# LuMini_1Inch.net
KiCad netlist of a schematic drawn in EAGLE
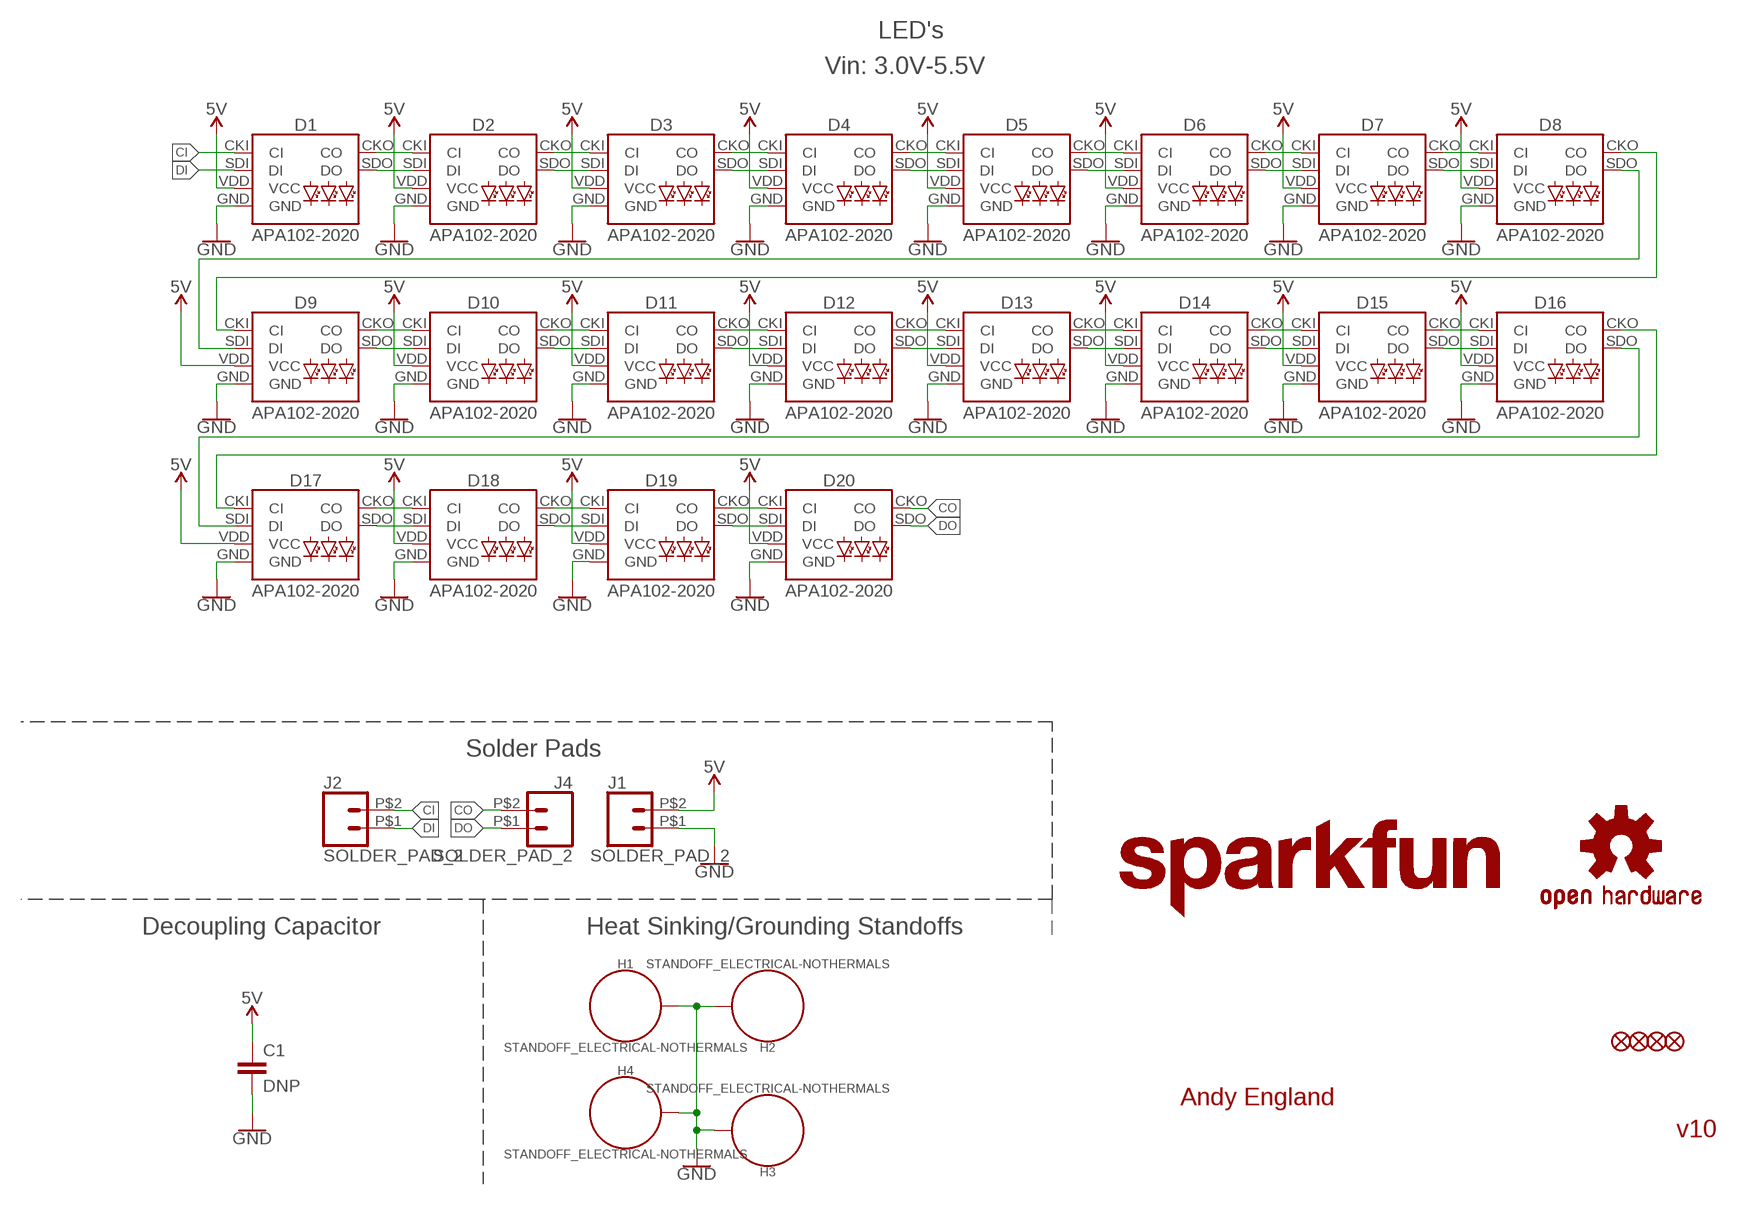
[diagram p0: schematic, sheet 1]

(export (version "E")
  (design (tool "Eeschema 10.0.6"))
  (components
    (comp (ref "C1")
      (value "DNP")
      (footprint "eagle-import:0603")
      (libsource (lib "eagle-import") (part "4.7UF-0603-6.3V-(10%)"))
    )
    (comp (ref "D1")
      (value "APA102-2020")
      (footprint "eagle-import:APA102-2020")
      (libsource (lib "eagle-import") (part "APA102-2020"))
    )
    (comp (ref "D2")
      (value "APA102-2020")
      (footprint "eagle-import:APA102-2020")
      (libsource (lib "eagle-import") (part "APA102-2020"))
    )
    (comp (ref "D3")
      (value "APA102-2020")
      (footprint "eagle-import:APA102-2020")
      (libsource (lib "eagle-import") (part "APA102-2020"))
    )
    (comp (ref "D4")
      (value "APA102-2020")
      (footprint "eagle-import:APA102-2020")
      (libsource (lib "eagle-import") (part "APA102-2020"))
    )
    (comp (ref "D5")
      (value "APA102-2020")
      (footprint "eagle-import:APA102-2020")
      (libsource (lib "eagle-import") (part "APA102-2020"))
    )
    (comp (ref "D6")
      (value "APA102-2020")
      (footprint "eagle-import:APA102-2020")
      (libsource (lib "eagle-import") (part "APA102-2020"))
    )
    (comp (ref "D7")
      (value "APA102-2020")
      (footprint "eagle-import:APA102-2020")
      (libsource (lib "eagle-import") (part "APA102-2020"))
    )
    (comp (ref "D8")
      (value "APA102-2020")
      (footprint "eagle-import:APA102-2020")
      (libsource (lib "eagle-import") (part "APA102-2020"))
    )
    (comp (ref "D9")
      (value "APA102-2020")
      (footprint "eagle-import:APA102-2020")
      (libsource (lib "eagle-import") (part "APA102-2020"))
    )
    (comp (ref "D10")
      (value "APA102-2020")
      (footprint "eagle-import:APA102-2020")
      (libsource (lib "eagle-import") (part "APA102-2020"))
    )
    (comp (ref "D11")
      (value "APA102-2020")
      (footprint "eagle-import:APA102-2020")
      (libsource (lib "eagle-import") (part "APA102-2020"))
    )
    (comp (ref "D12")
      (value "APA102-2020")
      (footprint "eagle-import:APA102-2020")
      (libsource (lib "eagle-import") (part "APA102-2020"))
    )
    (comp (ref "D13")
      (value "APA102-2020")
      (footprint "eagle-import:APA102-2020")
      (libsource (lib "eagle-import") (part "APA102-2020"))
    )
    (comp (ref "D14")
      (value "APA102-2020")
      (footprint "eagle-import:APA102-2020")
      (libsource (lib "eagle-import") (part "APA102-2020"))
    )
    (comp (ref "D15")
      (value "APA102-2020")
      (footprint "eagle-import:APA102-2020")
      (libsource (lib "eagle-import") (part "APA102-2020"))
    )
    (comp (ref "D16")
      (value "APA102-2020")
      (footprint "eagle-import:APA102-2020")
      (libsource (lib "eagle-import") (part "APA102-2020"))
    )
    (comp (ref "D17")
      (value "APA102-2020")
      (footprint "eagle-import:APA102-2020")
      (libsource (lib "eagle-import") (part "APA102-2020"))
    )
    (comp (ref "D18")
      (value "APA102-2020")
      (footprint "eagle-import:APA102-2020")
      (libsource (lib "eagle-import") (part "APA102-2020"))
    )
    (comp (ref "D19")
      (value "APA102-2020")
      (footprint "eagle-import:APA102-2020")
      (libsource (lib "eagle-import") (part "APA102-2020"))
    )
    (comp (ref "D20")
      (value "APA102-2020")
      (footprint "eagle-import:APA102-2020")
      (libsource (lib "eagle-import") (part "APA102-2020"))
    )
    (comp (ref "FD1")
      (value "FIDUCIALUFIDUCIAL")
      (footprint "eagle-import:FIDUCIAL-MICRO")
      (libsource (lib "eagle-import") (part "FIDUCIALUFIDUCIAL"))
    )
    (comp (ref "FD2")
      (value "FIDUCIALUFIDUCIAL")
      (footprint "eagle-import:FIDUCIAL-MICRO")
      (libsource (lib "eagle-import") (part "FIDUCIALUFIDUCIAL"))
    )
    (comp (ref "FD3")
      (value "FIDUCIALUFIDUCIAL")
      (footprint "eagle-import:FIDUCIAL-MICRO")
      (libsource (lib "eagle-import") (part "FIDUCIALUFIDUCIAL"))
    )
    (comp (ref "FD4")
      (value "FIDUCIALUFIDUCIAL")
      (footprint "eagle-import:FIDUCIAL-MICRO")
      (libsource (lib "eagle-import") (part "FIDUCIALUFIDUCIAL"))
    )
    (comp (ref "H1")
      (value "STANDOFF_ELECTRICAL-NOTHERMALS")
      (footprint "eagle-import:STANDOFF-ELECTRICAL-NOTHERMALS")
      (libsource (lib "eagle-import") (part "STANDOFF_ELECTRICAL-NOTHERMALS"))
    )
    (comp (ref "H2")
      (value "STANDOFF_ELECTRICAL-NOTHERMALS")
      (footprint "eagle-import:STANDOFF-ELECTRICAL-NOTHERMALS")
      (libsource (lib "eagle-import") (part "STANDOFF_ELECTRICAL-NOTHERMALS"))
    )
    (comp (ref "H3")
      (value "STANDOFF_ELECTRICAL-NOTHERMALS")
      (footprint "eagle-import:STANDOFF-ELECTRICAL-NOTHERMALS")
      (libsource (lib "eagle-import") (part "STANDOFF_ELECTRICAL-NOTHERMALS"))
    )
    (comp (ref "H4")
      (value "STANDOFF_ELECTRICAL-NOTHERMALS")
      (footprint "eagle-import:STANDOFF-ELECTRICAL-NOTHERMALS")
      (libsource (lib "eagle-import") (part "STANDOFF_ELECTRICAL-NOTHERMALS"))
    )
    (comp (ref "J1")
      (value "SOLDER_PAD_2")
      (footprint "eagle-import:SOLDER_PAD_2")
      (libsource (lib "eagle-import") (part "SOLDER_PAD_2"))
    )
    (comp (ref "J2")
      (value "SOLDER_PAD_2")
      (footprint "eagle-import:SOLDER_PAD_2")
      (libsource (lib "eagle-import") (part "SOLDER_PAD_2"))
    )
    (comp (ref "J4")
      (value "SOLDER_PAD_2")
      (footprint "eagle-import:SOLDER_PAD_2")
      (libsource (lib "eagle-import") (part "SOLDER_PAD_2"))
    )
    (comp (ref "LOGO1")
      (value "SFE_LOGO_NAME.1_INCH")
      (footprint "eagle-import:SFE_LOGO_NAME_.1")
      (libsource (lib "eagle-import") (part "SFE_LOGO_NAME.1_INCH"))
    )
    (comp (ref "LOGO2")
      (value "OSHW-LOGOS")
      (footprint "eagle-import:OSHW-LOGO-S")
      (libsource (lib "eagle-import") (part "OSHW-LOGOS"))
    )
  )
  (nets
    (net (code "1") (name "5V") (class "Default")
      (node (ref "C1") (pin "1") (pinfunction "1_1") (pintype "passive"))
      (node (ref "D1") (pin "VDD") (pinfunction "VCC_VDD") (pintype "bidirectional"))
      (node (ref "D10") (pin "VDD") (pinfunction "VCC_VDD") (pintype "bidirectional"))
      (node (ref "D11") (pin "VDD") (pinfunction "VCC_VDD") (pintype "bidirectional"))
      (node (ref "D12") (pin "VDD") (pinfunction "VCC_VDD") (pintype "bidirectional"))
      (node (ref "D13") (pin "VDD") (pinfunction "VCC_VDD") (pintype "bidirectional"))
      (node (ref "D14") (pin "VDD") (pinfunction "VCC_VDD") (pintype "bidirectional"))
      (node (ref "D15") (pin "VDD") (pinfunction "VCC_VDD") (pintype "bidirectional"))
      (node (ref "D16") (pin "VDD") (pinfunction "VCC_VDD") (pintype "bidirectional"))
      (node (ref "D17") (pin "VDD") (pinfunction "VCC_VDD") (pintype "bidirectional"))
      (node (ref "D18") (pin "VDD") (pinfunction "VCC_VDD") (pintype "bidirectional"))
      (node (ref "D19") (pin "VDD") (pinfunction "VCC_VDD") (pintype "bidirectional"))
      (node (ref "D2") (pin "VDD") (pinfunction "VCC_VDD") (pintype "bidirectional"))
      (node (ref "D20") (pin "VDD") (pinfunction "VCC_VDD") (pintype "bidirectional"))
      (node (ref "D3") (pin "VDD") (pinfunction "VCC_VDD") (pintype "bidirectional"))
      (node (ref "D4") (pin "VDD") (pinfunction "VCC_VDD") (pintype "bidirectional"))
      (node (ref "D5") (pin "VDD") (pinfunction "VCC_VDD") (pintype "bidirectional"))
      (node (ref "D6") (pin "VDD") (pinfunction "VCC_VDD") (pintype "bidirectional"))
      (node (ref "D7") (pin "VDD") (pinfunction "VCC_VDD") (pintype "bidirectional"))
      (node (ref "D8") (pin "VDD") (pinfunction "VCC_VDD") (pintype "bidirectional"))
      (node (ref "D9") (pin "VDD") (pinfunction "VCC_VDD") (pintype "bidirectional"))
      (node (ref "J1") (pin "P$2") (pinfunction "2_P$2") (pintype "passive"))
    )
    (net (code "2") (name "CI") (class "Default")
      (node (ref "D1") (pin "CKI") (pinfunction "CI_CKI") (pintype "bidirectional"))
      (node (ref "J2") (pin "P$2") (pinfunction "2_P$2") (pintype "passive"))
    )
    (net (code "3") (name "CO") (class "Default")
      (node (ref "D20") (pin "CKO") (pinfunction "CO_CKO") (pintype "bidirectional"))
      (node (ref "J4") (pin "P$2") (pinfunction "2_P$2") (pintype "passive"))
    )
    (net (code "4") (name "DI") (class "Default")
      (node (ref "D1") (pin "SDI") (pinfunction "DI_SDI") (pintype "bidirectional"))
      (node (ref "J2") (pin "P$1") (pinfunction "1_P$1") (pintype "passive"))
    )
    (net (code "5") (name "DO") (class "Default")
      (node (ref "D20") (pin "SDO") (pinfunction "DO_SDO") (pintype "bidirectional"))
      (node (ref "J4") (pin "P$1") (pinfunction "1_P$1") (pintype "passive"))
    )
    (net (code "6") (name "GND") (class "Default")
      (node (ref "C1") (pin "2") (pinfunction "2_2") (pintype "passive"))
      (node (ref "D1") (pin "GND") (pinfunction "GND_GND") (pintype "bidirectional"))
      (node (ref "D10") (pin "GND") (pinfunction "GND_GND") (pintype "bidirectional"))
      (node (ref "D11") (pin "GND") (pinfunction "GND_GND") (pintype "bidirectional"))
      (node (ref "D12") (pin "GND") (pinfunction "GND_GND") (pintype "bidirectional"))
      (node (ref "D13") (pin "GND") (pinfunction "GND_GND") (pintype "bidirectional"))
      (node (ref "D14") (pin "GND") (pinfunction "GND_GND") (pintype "bidirectional"))
      (node (ref "D15") (pin "GND") (pinfunction "GND_GND") (pintype "bidirectional"))
      (node (ref "D16") (pin "GND") (pinfunction "GND_GND") (pintype "bidirectional"))
      (node (ref "D17") (pin "GND") (pinfunction "GND_GND") (pintype "bidirectional"))
      (node (ref "D18") (pin "GND") (pinfunction "GND_GND") (pintype "bidirectional"))
      (node (ref "D19") (pin "GND") (pinfunction "GND_GND") (pintype "bidirectional"))
      (node (ref "D2") (pin "GND") (pinfunction "GND_GND") (pintype "bidirectional"))
      (node (ref "D20") (pin "GND") (pinfunction "GND_GND") (pintype "bidirectional"))
      (node (ref "D3") (pin "GND") (pinfunction "GND_GND") (pintype "bidirectional"))
      (node (ref "D4") (pin "GND") (pinfunction "GND_GND") (pintype "bidirectional"))
      (node (ref "D5") (pin "GND") (pinfunction "GND_GND") (pintype "bidirectional"))
      (node (ref "D6") (pin "GND") (pinfunction "GND_GND") (pintype "bidirectional"))
      (node (ref "D7") (pin "GND") (pinfunction "GND_GND") (pintype "bidirectional"))
      (node (ref "D8") (pin "GND") (pinfunction "GND_GND") (pintype "bidirectional"))
      (node (ref "D9") (pin "GND") (pinfunction "GND_GND") (pintype "bidirectional"))
      (node (ref "H1") (pin "P1") (pinfunction "P$1_P1") (pintype "bidirectional"))
      (node (ref "H2") (pin "P1") (pinfunction "P$1_P1") (pintype "bidirectional"))
      (node (ref "H3") (pin "P1") (pinfunction "P$1_P1") (pintype "bidirectional"))
      (node (ref "H4") (pin "P1") (pinfunction "P$1_P1") (pintype "bidirectional"))
      (node (ref "J1") (pin "P$1") (pinfunction "1_P$1") (pintype "passive"))
    )
    (net (code "7") (name "Net-(D1-CO)") (class "Default")
      (node (ref "D1") (pin "CKO") (pinfunction "CO_CKO") (pintype "bidirectional"))
      (node (ref "D2") (pin "CKI") (pinfunction "CI_CKI") (pintype "bidirectional"))
    )
    (net (code "8") (name "Net-(D1-DO)") (class "Default")
      (node (ref "D1") (pin "SDO") (pinfunction "DO_SDO") (pintype "bidirectional"))
      (node (ref "D2") (pin "SDI") (pinfunction "DI_SDI") (pintype "bidirectional"))
    )
    (net (code "9") (name "Net-(D2-CO)") (class "Default")
      (node (ref "D2") (pin "CKO") (pinfunction "CO_CKO") (pintype "bidirectional"))
      (node (ref "D3") (pin "CKI") (pinfunction "CI_CKI") (pintype "bidirectional"))
    )
    (net (code "10") (name "Net-(D2-DO)") (class "Default")
      (node (ref "D2") (pin "SDO") (pinfunction "DO_SDO") (pintype "bidirectional"))
      (node (ref "D3") (pin "SDI") (pinfunction "DI_SDI") (pintype "bidirectional"))
    )
    (net (code "11") (name "Net-(D3-CO)") (class "Default")
      (node (ref "D3") (pin "CKO") (pinfunction "CO_CKO") (pintype "bidirectional"))
      (node (ref "D4") (pin "CKI") (pinfunction "CI_CKI") (pintype "bidirectional"))
    )
    (net (code "12") (name "Net-(D3-DO)") (class "Default")
      (node (ref "D3") (pin "SDO") (pinfunction "DO_SDO") (pintype "bidirectional"))
      (node (ref "D4") (pin "SDI") (pinfunction "DI_SDI") (pintype "bidirectional"))
    )
    (net (code "13") (name "Net-(D4-CO)") (class "Default")
      (node (ref "D4") (pin "CKO") (pinfunction "CO_CKO") (pintype "bidirectional"))
      (node (ref "D5") (pin "CKI") (pinfunction "CI_CKI") (pintype "bidirectional"))
    )
    (net (code "14") (name "Net-(D4-DO)") (class "Default")
      (node (ref "D4") (pin "SDO") (pinfunction "DO_SDO") (pintype "bidirectional"))
      (node (ref "D5") (pin "SDI") (pinfunction "DI_SDI") (pintype "bidirectional"))
    )
    (net (code "15") (name "Net-(D5-CO)") (class "Default")
      (node (ref "D5") (pin "CKO") (pinfunction "CO_CKO") (pintype "bidirectional"))
      (node (ref "D6") (pin "CKI") (pinfunction "CI_CKI") (pintype "bidirectional"))
    )
    (net (code "16") (name "Net-(D5-DO)") (class "Default")
      (node (ref "D5") (pin "SDO") (pinfunction "DO_SDO") (pintype "bidirectional"))
      (node (ref "D6") (pin "SDI") (pinfunction "DI_SDI") (pintype "bidirectional"))
    )
    (net (code "17") (name "Net-(D6-CO)") (class "Default")
      (node (ref "D6") (pin "CKO") (pinfunction "CO_CKO") (pintype "bidirectional"))
      (node (ref "D7") (pin "CKI") (pinfunction "CI_CKI") (pintype "bidirectional"))
    )
    (net (code "18") (name "Net-(D6-DO)") (class "Default")
      (node (ref "D6") (pin "SDO") (pinfunction "DO_SDO") (pintype "bidirectional"))
      (node (ref "D7") (pin "SDI") (pinfunction "DI_SDI") (pintype "bidirectional"))
    )
    (net (code "19") (name "Net-(D7-CO)") (class "Default")
      (node (ref "D7") (pin "CKO") (pinfunction "CO_CKO") (pintype "bidirectional"))
      (node (ref "D8") (pin "CKI") (pinfunction "CI_CKI") (pintype "bidirectional"))
    )
    (net (code "20") (name "Net-(D7-DO)") (class "Default")
      (node (ref "D7") (pin "SDO") (pinfunction "DO_SDO") (pintype "bidirectional"))
      (node (ref "D8") (pin "SDI") (pinfunction "DI_SDI") (pintype "bidirectional"))
    )
    (net (code "21") (name "Net-(D8-CO)") (class "Default")
      (node (ref "D8") (pin "CKO") (pinfunction "CO_CKO") (pintype "bidirectional"))
      (node (ref "D9") (pin "CKI") (pinfunction "CI_CKI") (pintype "bidirectional"))
    )
    (net (code "22") (name "Net-(D8-DO)") (class "Default")
      (node (ref "D8") (pin "SDO") (pinfunction "DO_SDO") (pintype "bidirectional"))
      (node (ref "D9") (pin "SDI") (pinfunction "DI_SDI") (pintype "bidirectional"))
    )
    (net (code "23") (name "Net-(D10-CI)") (class "Default")
      (node (ref "D10") (pin "CKI") (pinfunction "CI_CKI") (pintype "bidirectional"))
      (node (ref "D9") (pin "CKO") (pinfunction "CO_CKO") (pintype "bidirectional"))
    )
    (net (code "24") (name "Net-(D10-CO)") (class "Default")
      (node (ref "D10") (pin "CKO") (pinfunction "CO_CKO") (pintype "bidirectional"))
      (node (ref "D11") (pin "CKI") (pinfunction "CI_CKI") (pintype "bidirectional"))
    )
    (net (code "25") (name "Net-(D10-DI)") (class "Default")
      (node (ref "D10") (pin "SDI") (pinfunction "DI_SDI") (pintype "bidirectional"))
      (node (ref "D9") (pin "SDO") (pinfunction "DO_SDO") (pintype "bidirectional"))
    )
    (net (code "26") (name "Net-(D10-DO)") (class "Default")
      (node (ref "D10") (pin "SDO") (pinfunction "DO_SDO") (pintype "bidirectional"))
      (node (ref "D11") (pin "SDI") (pinfunction "DI_SDI") (pintype "bidirectional"))
    )
    (net (code "27") (name "Net-(D11-CO)") (class "Default")
      (node (ref "D11") (pin "CKO") (pinfunction "CO_CKO") (pintype "bidirectional"))
      (node (ref "D12") (pin "CKI") (pinfunction "CI_CKI") (pintype "bidirectional"))
    )
    (net (code "28") (name "Net-(D11-DO)") (class "Default")
      (node (ref "D11") (pin "SDO") (pinfunction "DO_SDO") (pintype "bidirectional"))
      (node (ref "D12") (pin "SDI") (pinfunction "DI_SDI") (pintype "bidirectional"))
    )
    (net (code "29") (name "Net-(D12-CO)") (class "Default")
      (node (ref "D12") (pin "CKO") (pinfunction "CO_CKO") (pintype "bidirectional"))
      (node (ref "D13") (pin "CKI") (pinfunction "CI_CKI") (pintype "bidirectional"))
    )
    (net (code "30") (name "Net-(D12-DO)") (class "Default")
      (node (ref "D12") (pin "SDO") (pinfunction "DO_SDO") (pintype "bidirectional"))
      (node (ref "D13") (pin "SDI") (pinfunction "DI_SDI") (pintype "bidirectional"))
    )
    (net (code "31") (name "Net-(D13-CO)") (class "Default")
      (node (ref "D13") (pin "CKO") (pinfunction "CO_CKO") (pintype "bidirectional"))
      (node (ref "D14") (pin "CKI") (pinfunction "CI_CKI") (pintype "bidirectional"))
    )
    (net (code "32") (name "Net-(D13-DO)") (class "Default")
      (node (ref "D13") (pin "SDO") (pinfunction "DO_SDO") (pintype "bidirectional"))
      (node (ref "D14") (pin "SDI") (pinfunction "DI_SDI") (pintype "bidirectional"))
    )
    (net (code "33") (name "Net-(D14-CO)") (class "Default")
      (node (ref "D14") (pin "CKO") (pinfunction "CO_CKO") (pintype "bidirectional"))
      (node (ref "D15") (pin "CKI") (pinfunction "CI_CKI") (pintype "bidirectional"))
    )
    (net (code "34") (name "Net-(D14-DO)") (class "Default")
      (node (ref "D14") (pin "SDO") (pinfunction "DO_SDO") (pintype "bidirectional"))
      (node (ref "D15") (pin "SDI") (pinfunction "DI_SDI") (pintype "bidirectional"))
    )
    (net (code "35") (name "Net-(D15-CO)") (class "Default")
      (node (ref "D15") (pin "CKO") (pinfunction "CO_CKO") (pintype "bidirectional"))
      (node (ref "D16") (pin "CKI") (pinfunction "CI_CKI") (pintype "bidirectional"))
    )
    (net (code "36") (name "Net-(D15-DO)") (class "Default")
      (node (ref "D15") (pin "SDO") (pinfunction "DO_SDO") (pintype "bidirectional"))
      (node (ref "D16") (pin "SDI") (pinfunction "DI_SDI") (pintype "bidirectional"))
    )
    (net (code "37") (name "Net-(D16-CO)") (class "Default")
      (node (ref "D16") (pin "CKO") (pinfunction "CO_CKO") (pintype "bidirectional"))
      (node (ref "D17") (pin "CKI") (pinfunction "CI_CKI") (pintype "bidirectional"))
    )
    (net (code "38") (name "Net-(D16-DO)") (class "Default")
      (node (ref "D16") (pin "SDO") (pinfunction "DO_SDO") (pintype "bidirectional"))
      (node (ref "D17") (pin "SDI") (pinfunction "DI_SDI") (pintype "bidirectional"))
    )
    (net (code "39") (name "Net-(D17-CO)") (class "Default")
      (node (ref "D17") (pin "CKO") (pinfunction "CO_CKO") (pintype "bidirectional"))
      (node (ref "D18") (pin "CKI") (pinfunction "CI_CKI") (pintype "bidirectional"))
    )
    (net (code "40") (name "Net-(D17-DO)") (class "Default")
      (node (ref "D17") (pin "SDO") (pinfunction "DO_SDO") (pintype "bidirectional"))
      (node (ref "D18") (pin "SDI") (pinfunction "DI_SDI") (pintype "bidirectional"))
    )
    (net (code "41") (name "Net-(D18-CO)") (class "Default")
      (node (ref "D18") (pin "CKO") (pinfunction "CO_CKO") (pintype "bidirectional"))
      (node (ref "D19") (pin "CKI") (pinfunction "CI_CKI") (pintype "bidirectional"))
    )
    (net (code "42") (name "Net-(D18-DO)") (class "Default")
      (node (ref "D18") (pin "SDO") (pinfunction "DO_SDO") (pintype "bidirectional"))
      (node (ref "D19") (pin "SDI") (pinfunction "DI_SDI") (pintype "bidirectional"))
    )
    (net (code "43") (name "Net-(D19-CO)") (class "Default")
      (node (ref "D19") (pin "CKO") (pinfunction "CO_CKO") (pintype "bidirectional"))
      (node (ref "D20") (pin "CKI") (pinfunction "CI_CKI") (pintype "bidirectional"))
    )
    (net (code "44") (name "Net-(D19-DO)") (class "Default")
      (node (ref "D19") (pin "SDO") (pinfunction "DO_SDO") (pintype "bidirectional"))
      (node (ref "D20") (pin "SDI") (pinfunction "DI_SDI") (pintype "bidirectional"))
    )
  )
)
